# node.net
KiCad netlist of a schematic drawn in Altium Designer
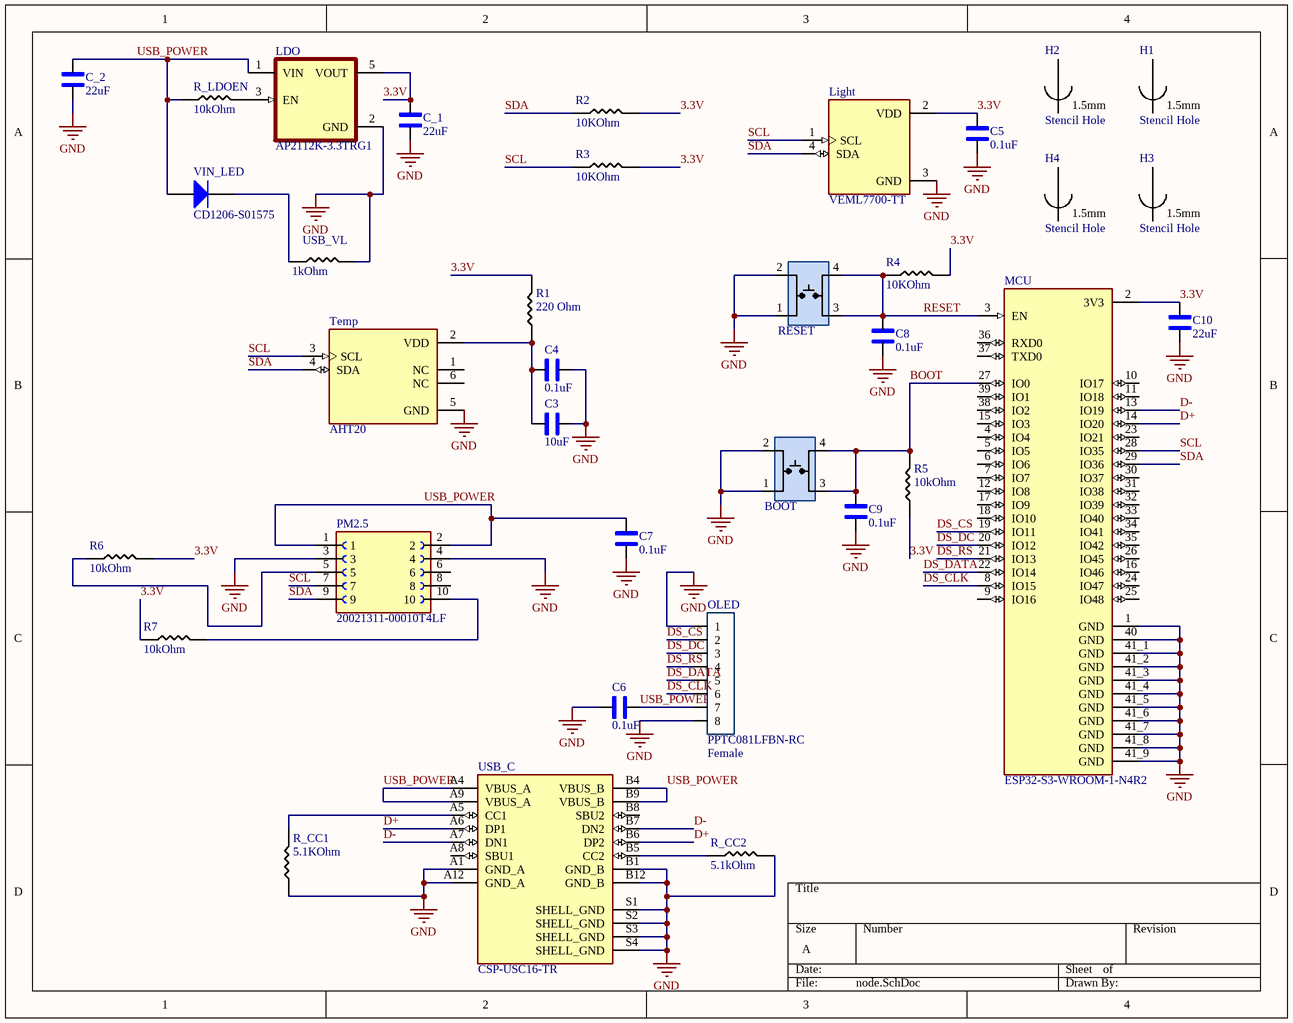
[diagram p0: node.SchDoc]

(export (version "E")
  (design (tool "Eeschema 10.0.6"))
  (components
    (comp (ref "BOOT")
      (value "TL3305AF160QG")
      (footprint "Switch_JLC")
      (description "Tactile Switch SPST-NO Top Actuated Surface Mount")
      (fields (field (name "MFR PART #") "KH-4.5X4.5X4.3H-STM") (field (name "LCSC PART#") "C2837550"))
      (libsource (lib "ECEN5730Lib_2023_01_DS") (part "SW_Push_Button_JLC"))
    )
    (comp (ref "C3")
      (value "10uF")
      (footprint "1206_Passive_Capacitor")
      (description "10uF ±10% 50V X5R 1206 Multilayer Ceramic Capacitors MLCC - SMD/SMT RoHS")
      (fields (field (name "LCSC PART#") "C13585") (field (name "MFR PART #") "CL31A106KBHNNNE"))
      (libsource (lib "ECEN5730Lib_2023_01_DS") (part "C_10uF_1206"))
    )
    (comp (ref "C4")
      (value "0.1uF")
      (footprint "1206_Passive_Capacitor")
      (description "10uF ±10% 50V X5R 1206 Multilayer Ceramic Capacitors MLCC - SMD/SMT RoHS")
      (fields (field (name "LCSC PART#") "C13585") (field (name "MFR PART #") "CL31A106KBHNNNE"))
      (libsource (lib "ECEN5730Lib_2023_01_DS") (part "C_10uF_1206"))
    )
    (comp (ref "C5")
      (value "0.1uF")
      (footprint "1206_Passive_Capacitor")
      (description "10uF ±10% 50V X5R 1206 Multilayer Ceramic Capacitors MLCC - SMD/SMT RoHS")
      (fields (field (name "LCSC PART#") "C13585") (field (name "MFR PART #") "CL31A106KBHNNNE"))
      (libsource (lib "ECEN5730Lib_2023_01_DS") (part "C_10uF_1206"))
    )
    (comp (ref "C6")
      (value "0.1uF")
      (footprint "1206_Passive_Capacitor")
      (description "10uF ±10% 50V X5R 1206 Multilayer Ceramic Capacitors MLCC - SMD/SMT RoHS")
      (fields (field (name "LCSC PART#") "C13585") (field (name "MFR PART #") "CL31A106KBHNNNE"))
      (libsource (lib "ECEN5730Lib_2023_01_DS") (part "C_10uF_1206"))
    )
    (comp (ref "C7")
      (value "0.1uF")
      (footprint "1206_Passive_Capacitor")
      (description "10uF ±10% 50V X5R 1206 Multilayer Ceramic Capacitors MLCC - SMD/SMT RoHS")
      (fields (field (name "LCSC PART#") "C13585") (field (name "MFR PART #") "CL31A106KBHNNNE"))
      (libsource (lib "ECEN5730Lib_2023_01_DS") (part "C_10uF_1206"))
    )
    (comp (ref "C8")
      (value "0.1uF")
      (footprint "1206_Passive_Capacitor")
      (description "10uF ±10% 50V X5R 1206 Multilayer Ceramic Capacitors MLCC - SMD/SMT RoHS")
      (fields (field (name "LCSC PART#") "C13585") (field (name "MFR PART #") "CL31A106KBHNNNE"))
      (libsource (lib "ECEN5730Lib_2023_01_DS") (part "C_10uF_1206"))
    )
    (comp (ref "C9")
      (value "0.1uF")
      (footprint "1206_Passive_Capacitor")
      (description "10uF ±10% 50V X5R 1206 Multilayer Ceramic Capacitors MLCC - SMD/SMT RoHS")
      (fields (field (name "LCSC PART#") "C13585") (field (name "MFR PART #") "CL31A106KBHNNNE"))
      (libsource (lib "ECEN5730Lib_2023_01_DS") (part "C_10uF_1206"))
    )
    (comp (ref "C10")
      (value "22uF")
      (footprint "1206_Passive_Capacitor")
      (description "10uF ±10% 50V X5R 1206 Multilayer Ceramic Capacitors MLCC - SMD/SMT RoHS")
      (fields (field (name "LCSC PART#") "C13585") (field (name "MFR PART #") "CL31A106KBHNNNE"))
      (libsource (lib "ECEN5730Lib_2023_01_DS") (part "C_10uF_1206"))
    )
    (comp (ref "C_1")
      (value "22uF")
      (footprint "1206_Passive_Capacitor")
      (description "22uF ±10% 25V X5R 1206 Multilayer Ceramic Capacitors MLCC - SMD/SMT RoHS")
      (fields (field (name "MFR PART #") "CL31A226KAHNNNE") (field (name "LCSC PART#") "C12891"))
      (libsource (lib "ECEN5730Lib_2023_01_DS") (part "C_22uF_1206"))
    )
    (comp (ref "C_2")
      (value "22uF")
      (footprint "1206_Passive_Capacitor")
      (description "22uF ±10% 25V X5R 1206 Multilayer Ceramic Capacitors MLCC - SMD/SMT RoHS")
      (fields (field (name "MFR PART #") "CL31A226KAHNNNE") (field (name "LCSC PART#") "C12891"))
      (libsource (lib "ECEN5730Lib_2023_01_DS") (part "C_22uF_1206"))
    )
    (comp (ref "H1")
      (value "Stencil Hole")
      (footprint "AlignmentHole_1.5mm")
      (description "Stencil Allignment hole for use with 1.5mm pin")
      (libsource (lib "ECEN5730Lib_2023_01_DS") (part "H_StencilAllignment_1.5mm"))
    )
    (comp (ref "H2")
      (value "Stencil Hole")
      (footprint "AlignmentHole_1.5mm")
      (description "Stencil Allignment hole for use with 1.5mm pin")
      (libsource (lib "ECEN5730Lib_2023_01_DS") (part "H_StencilAllignment_1.5mm"))
    )
    (comp (ref "H3")
      (value "Stencil Hole")
      (footprint "AlignmentHole_1.5mm")
      (description "Stencil Allignment hole for use with 1.5mm pin")
      (libsource (lib "ECEN5730Lib_2023_01_DS") (part "H_StencilAllignment_1.5mm"))
    )
    (comp (ref "H4")
      (value "Stencil Hole")
      (footprint "AlignmentHole_1.5mm")
      (description "Stencil Allignment hole for use with 1.5mm pin")
      (libsource (lib "ECEN5730Lib_2023_01_DS") (part "H_StencilAllignment_1.5mm"))
    )
    (comp (ref "LDO")
      (value "AP2112K-3.3TRG1")
      (footprint "AP2112K-3.3TRG1:SOT95P285X140-5N")
      (description "AP2112 Series 0.6 A 3.3 V Fixed Output SMT LDO Linear Regulator - SOT23-5")
      (fields (field (name "MF") "{'manufacturer': u'Diodes Inc.'}"))
      (libsource (lib "AP2112K-3.3TRG1") (part "AP2112K-3.3TRG1"))
    )
    (comp (ref "Light")
      (value "VEML7700-TT")
      (footprint "VEML7700-TT:XDCR_VEML7700-TT")
      (fields (field (name "MF") "{'manufacturer': u'Vishay Semiconductor'}"))
      (libsource (lib "*") (part "VEML7700-TT"))
    )
    (comp (ref "MCU")
      (value "ESP32-S3-WROOM-1-N4R2")
      (footprint "ESP32-S3-WROOM-1-N4R2:XCVR_ESP32-S3-WROOM-1-N4R2")
      (fields (field (name "MF") "{'manufacturer': u'Espressif Systems'}"))
      (libsource (lib "*") (part "ESP32-S3-WROOM-1-N4R2"))
    )
    (comp (ref "OLED")
      (value "PPTC081LFBN-RC")
      (footprint "8_PIN_100MIL - Female")
      (description "8 Position Header Connector 0.100\" (2.54mm) Through Hole Tin")
      (fields (field (name "LCSC PART#") "C27438") (field (name "ALTIUM_VALUE") "Female"))
      (libsource (lib "ECEN5730Lib_2023_01_DS") (part "JF_8_PIN_FEMALE"))
    )
    (comp (ref "PM2.5")
      (value "20021311-00010T4LF")
      (footprint "20021311-00010T4LF:AMPHENOL_20021311-00010T4LF")
      (fields (field (name "MF") "{'manufacturer': u'Amphenol ICC'}"))
      (libsource (lib "*") (part "20021311-00010T4LF"))
    )
    (comp (ref "R1")
      (value "220 Ohm")
      (footprint "1206_Passive_Resitor")
      (description "CHIP RESISTOR - SURFACE MOUNT 0OHMS ±1% 1/4W 1206 ROHS")
      (fields (field (name "MFR PART #") "1206W4F0000T5E") (field (name "LCSC PART#") "C17888"))
      (libsource (lib "ECEN5730Lib_2023_01_DS") (part "R_0Ohm_1206"))
    )
    (comp (ref "R2")
      (value "10KOhm")
      (footprint "1206_Passive_Resitor")
      (description "10 kOhms ±5% 0.25W, 1/4W Chip Resistor 1206 (3216 Metric) Automotive AEC-Q200 Thick Film")
      (fields (field (name "MFR PART #") "RMCF1206FT10K0") (field (name "LCSC PART#") "C17902"))
      (libsource (lib "ECEN5730Lib_2023_01_DS") (part "R_10KOhm_1206"))
    )
    (comp (ref "R3")
      (value "10KOhm")
      (footprint "1206_Passive_Resitor")
      (description "10 kOhms ±5% 0.25W, 1/4W Chip Resistor 1206 (3216 Metric) Automotive AEC-Q200 Thick Film")
      (fields (field (name "MFR PART #") "RMCF1206FT10K0") (field (name "LCSC PART#") "C17902"))
      (libsource (lib "ECEN5730Lib_2023_01_DS") (part "R_10KOhm_1206"))
    )
    (comp (ref "R4")
      (value "10KOhm")
      (footprint "1206_Passive_Resitor")
      (description "10 kOhms ±5% 0.25W, 1/4W Chip Resistor 1206 (3216 Metric) Automotive AEC-Q200 Thick Film")
      (fields (field (name "MFR PART #") "RMCF1206FT10K0") (field (name "LCSC PART#") "C17902"))
      (libsource (lib "ECEN5730Lib_2023_01_DS") (part "R_10KOhm_1206"))
    )
    (comp (ref "R5")
      (value "10kOhm")
      (footprint "1206_Passive_Resitor")
      (description "CHIP RESISTOR - SURFACE MOUNT 0OHMS ±1% 1/4W 1206 ROHS")
      (fields (field (name "MFR PART #") "1206W4F0000T5E") (field (name "LCSC PART#") "C17888"))
      (libsource (lib "ECEN5730Lib_2023_01_DS") (part "R_0Ohm_1206"))
    )
    (comp (ref "R6")
      (value "10kOhm")
      (footprint "1206_Passive_Resitor")
      (description "CHIP RESISTOR - SURFACE MOUNT 0OHMS ±1% 1/4W 1206 ROHS")
      (fields (field (name "MFR PART #") "1206W4F0000T5E") (field (name "LCSC PART#") "C17888"))
      (libsource (lib "ECEN5730Lib_2023_01_DS") (part "R_0Ohm_1206"))
    )
    (comp (ref "R7")
      (value "10kOhm")
      (footprint "1206_Passive_Resitor")
      (description "CHIP RESISTOR - SURFACE MOUNT 0OHMS ±1% 1/4W 1206 ROHS")
      (fields (field (name "MFR PART #") "1206W4F0000T5E") (field (name "LCSC PART#") "C17888"))
      (libsource (lib "ECEN5730Lib_2023_01_DS") (part "R_0Ohm_1206"))
    )
    (comp (ref "RESET")
      (value "TL3305AF160QG")
      (footprint "Switch_JLC")
      (description "Tactile Switch SPST-NO Top Actuated Surface Mount")
      (fields (field (name "MFR PART #") "KH-4.5X4.5X4.3H-STM") (field (name "LCSC PART#") "C2837550"))
      (libsource (lib "ECEN5730Lib_2023_01_DS") (part "SW_Push_Button_JLC"))
    )
    (comp (ref "R_CC1")
      (value "5.1KOhm")
      (footprint "1206_Passive_Resitor")
      (description "100kΩ ±1% 0.25W ±100ppm/℃ 1206 Chip Resistor - Surface Mount RoHS")
      (fields (field (name "LCSC PART#") "C17900") (field (name "MFR PART #") "1206W4F1003T5E"))
      (libsource (lib "ECEN5730Lib_2023_01_DS") (part "R_100KOhm_1206"))
    )
    (comp (ref "R_CC2")
      (value "5.1kOhm")
      (footprint "1206_Passive_Resitor")
      (description "100kΩ ±1% 0.25W ±100ppm/℃ 1206 Chip Resistor - Surface Mount RoHS")
      (fields (field (name "LCSC PART#") "C17900") (field (name "MFR PART #") "1206W4F1003T5E"))
      (libsource (lib "ECEN5730Lib_2023_01_DS") (part "R_100KOhm_1206"))
    )
    (comp (ref "R_LDOEN")
      (value "10kOhm")
      (footprint "1206_Passive_Resitor")
      (description "1Ω ±5% 0.25W ±400ppm/℃ 1206 Chip Resistor - Surface Mount RoHS")
      (fields (field (name "LCSC PART#") "C1409") (field (name "MFR PART #") "1206W4J010JT5E"))
      (libsource (lib "ECEN5730Lib_2023_01_DS") (part "R_1Ohm_1206"))
    )
    (comp (ref "Temp")
      (value "AHT20")
      (footprint "AHT20:PSON100P300X300X110-6N")
      (description "Temperature and Humidity sensor")
      (fields (field (name "MF") "{'manufacturer': u'Asair'}"))
      (libsource (lib "*") (part "AHT20"))
    )
    (comp (ref "USB_C")
      (value "CSP-USC16-TR")
      (footprint "CSP-USC16-TR:VALCON_CSP-USC16-TR")
      (fields (field (name "MF") "{'manufacturer': u'Valcon'}"))
      (libsource (lib "*") (part "CSP-USC16-TR"))
    )
    (comp (ref "USB_VL")
      (value "1kOhm")
      (footprint "1206_Passive_Resitor")
      (description "100Ω ±1% 0.25W ±100ppm/℃ 1206 Chip Resistor - Surface Mount RoHS")
      (fields (field (name "LCSC PART#") "C17901") (field (name "MFR PART #") "1206W4F1000T5E"))
      (libsource (lib "ECEN5730Lib_2023_01_DS") (part "R_100Ohm_1206"))
    )
    (comp (ref "VIN_LED")
      (value "CD1206-S01575")
      (footprint "BOUR-CD1206-S01575-2_L")
      (description "75 V Small Signal Switching Diode, 150 mA, 2.5 uA, 1026 Molded Package, RoHS, Tape and Reel")
      (fields (field (name "MANUFACTURER") "Bourns"))
      (libsource (lib "Altium Content Vault") (part "BOUR-A1K2-2"))
    )
  )
  (nets
    (net (code "1") (name "/3.3V") (class "Default")
      (node (ref "C10") (pin "2") (pinfunction "2_2") (pintype "passive"))
      (node (ref "C5") (pin "2") (pinfunction "2_2") (pintype "passive"))
      (node (ref "C_1") (pin "2") (pinfunction "2_2") (pintype "passive"))
      (node (ref "LDO") (pin "5") (pinfunction "VOUT_5") (pintype "power_in"))
      (node (ref "Light") (pin "2") (pinfunction "VDD_2") (pintype "power_in"))
      (node (ref "MCU") (pin "2") (pinfunction "3V3_2") (pintype "power_in"))
      (node (ref "R1") (pin "2") (pinfunction "2_2") (pintype "passive"))
      (node (ref "R2") (pin "2") (pinfunction "2_2") (pintype "passive"))
      (node (ref "R3") (pin "2") (pinfunction "2_2") (pintype "passive"))
      (node (ref "R4") (pin "2") (pinfunction "2_2") (pintype "passive"))
      (node (ref "R5") (pin "1") (pinfunction "1_1") (pintype "passive"))
      (node (ref "R6") (pin "2") (pinfunction "2_2") (pintype "passive"))
      (node (ref "R7") (pin "1") (pinfunction "1_1") (pintype "passive"))
    )
    (net (code "3") (name "/BOOT") (class "Default")
      (node (ref "BOOT") (pin "3") (pinfunction "3_3") (pintype "passive"))
      (node (ref "BOOT") (pin "4") (pinfunction "4_4") (pintype "passive"))
      (node (ref "C9") (pin "2") (pinfunction "2_2") (pintype "passive"))
      (node (ref "MCU") (pin "27") (pinfunction "IO0_27") (pintype "bidirectional"))
      (node (ref "R5") (pin "2") (pinfunction "2_2") (pintype "passive"))
    )
    (net (code "4") (name "/D+") (class "Default")
      (node (ref "MCU") (pin "14") (pinfunction "IO20_14") (pintype "bidirectional"))
      (node (ref "USB_C") (pin "A6") (pinfunction "DP1_A6") (pintype "bidirectional"))
      (node (ref "USB_C") (pin "B6") (pinfunction "DP2_B6") (pintype "bidirectional"))
    )
    (net (code "5") (name "/D-") (class "Default")
      (node (ref "MCU") (pin "13") (pinfunction "IO19_13") (pintype "bidirectional"))
      (node (ref "USB_C") (pin "A7") (pinfunction "DN1_A7") (pintype "bidirectional"))
      (node (ref "USB_C") (pin "B7") (pinfunction "DN2_B7") (pintype "bidirectional"))
    )
    (net (code "6") (name "/DS_CLK") (class "Default")
      (node (ref "MCU") (pin "8") (pinfunction "IO15_8") (pintype "bidirectional"))
      (node (ref "OLED") (pin "6") (pinfunction "6_6") (pintype "passive"))
    )
    (net (code "7") (name "/DS_CS") (class "Default")
      (node (ref "MCU") (pin "19") (pinfunction "IO11_19") (pintype "bidirectional"))
      (node (ref "OLED") (pin "2") (pinfunction "2_2") (pintype "passive"))
    )
    (net (code "8") (name "/DS_DATA") (class "Default")
      (node (ref "MCU") (pin "22") (pinfunction "IO14_22") (pintype "bidirectional"))
      (node (ref "OLED") (pin "5") (pinfunction "5_5") (pintype "passive"))
    )
    (net (code "9") (name "/DS_DC") (class "Default")
      (node (ref "MCU") (pin "20") (pinfunction "IO12_20") (pintype "bidirectional"))
      (node (ref "OLED") (pin "3") (pinfunction "3_3") (pintype "passive"))
    )
    (net (code "10") (name "/DS_RS") (class "Default")
      (node (ref "MCU") (pin "21") (pinfunction "IO13_21") (pintype "bidirectional"))
      (node (ref "OLED") (pin "4") (pinfunction "4_4") (pintype "passive"))
    )
    (net (code "11") (name "/RESET") (class "Default")
      (node (ref "C8") (pin "2") (pinfunction "2_2") (pintype "passive"))
      (node (ref "MCU") (pin "3") (pinfunction "EN_3") (pintype "input"))
      (node (ref "R4") (pin "1") (pinfunction "1_1") (pintype "passive"))
      (node (ref "RESET") (pin "3") (pinfunction "3_3") (pintype "passive"))
      (node (ref "RESET") (pin "4") (pinfunction "4_4") (pintype "passive"))
    )
    (net (code "12") (name "/SCL") (class "Default")
      (node (ref "Light") (pin "1") (pinfunction "SCL_1") (pintype "input"))
      (node (ref "MCU") (pin "28") (pinfunction "IO35_28") (pintype "bidirectional"))
      (node (ref "PM2.5") (pin "7") (pinfunction "7_7") (pintype "passive"))
      (node (ref "R3") (pin "1") (pinfunction "1_1") (pintype "passive"))
      (node (ref "Temp") (pin "3") (pinfunction "SCL_3") (pintype "input"))
    )
    (net (code "13") (name "/SDA") (class "Default")
      (node (ref "Light") (pin "4") (pinfunction "SDA_4") (pintype "bidirectional"))
      (node (ref "MCU") (pin "29") (pinfunction "IO36_29") (pintype "bidirectional"))
      (node (ref "PM2.5") (pin "9") (pinfunction "9_9") (pintype "passive"))
      (node (ref "R2") (pin "1") (pinfunction "1_1") (pintype "passive"))
      (node (ref "Temp") (pin "4") (pinfunction "SDA_4") (pintype "bidirectional"))
    )
    (net (code "14") (name "/USB_POWER") (class "Default")
      (node (ref "C6") (pin "2") (pinfunction "2_2") (pintype "passive"))
      (node (ref "C7") (pin "2") (pinfunction "2_2") (pintype "passive"))
      (node (ref "C_2") (pin "2") (pinfunction "2_2") (pintype "passive"))
      (node (ref "LDO") (pin "1") (pinfunction "VIN_1") (pintype "power_in"))
      (node (ref "OLED") (pin "7") (pinfunction "7_7") (pintype "passive"))
      (node (ref "PM2.5") (pin "1") (pinfunction "1_1") (pintype "passive"))
      (node (ref "PM2.5") (pin "2") (pinfunction "2_2") (pintype "passive"))
      (node (ref "R_LDOEN") (pin "1") (pinfunction "1_1") (pintype "passive"))
      (node (ref "USB_C") (pin "A4") (pinfunction "VBUS_A_A4") (pintype "power_in"))
      (node (ref "USB_C") (pin "A9") (pinfunction "VBUS_A_A9") (pintype "power_in"))
      (node (ref "USB_C") (pin "B4") (pinfunction "VBUS_B_B4") (pintype "power_in"))
      (node (ref "USB_C") (pin "B9") (pinfunction "VBUS_B_B9") (pintype "power_in"))
      (node (ref "VIN_LED") (pin "1") (pinfunction "A_1") (pintype "passive"))
    )
    (net (code "15") (name "GND") (class "Default")
      (node (ref "BOOT") (pin "1") (pinfunction "1_1") (pintype "passive"))
      (node (ref "BOOT") (pin "2") (pinfunction "2_2") (pintype "passive"))
      (node (ref "C10") (pin "1") (pinfunction "1_1") (pintype "passive"))
      (node (ref "C3") (pin "2") (pinfunction "2_2") (pintype "passive"))
      (node (ref "C4") (pin "2") (pinfunction "2_2") (pintype "passive"))
      (node (ref "C5") (pin "1") (pinfunction "1_1") (pintype "passive"))
      (node (ref "C6") (pin "1") (pinfunction "1_1") (pintype "passive"))
      (node (ref "C7") (pin "1") (pinfunction "1_1") (pintype "passive"))
      (node (ref "C8") (pin "1") (pinfunction "1_1") (pintype "passive"))
      (node (ref "C9") (pin "1") (pinfunction "1_1") (pintype "passive"))
      (node (ref "C_1") (pin "1") (pinfunction "1_1") (pintype "passive"))
      (node (ref "C_2") (pin "1") (pinfunction "1_1") (pintype "passive"))
      (node (ref "LDO") (pin "2") (pinfunction "GND_2") (pintype "power_in"))
      (node (ref "Light") (pin "3") (pinfunction "GND_3") (pintype "power_in"))
      (node (ref "MCU") (pin "1") (pinfunction "GND_1") (pintype "power_in"))
      (node (ref "MCU") (pin "40") (pinfunction "GND_40") (pintype "power_in"))
      (node (ref "MCU") (pin "41_1") (pinfunction "GND_41_1") (pintype "power_in"))
      (node (ref "MCU") (pin "41_2") (pinfunction "GND_41_2") (pintype "power_in"))
      (node (ref "MCU") (pin "41_3") (pinfunction "GND_41_3") (pintype "power_in"))
      (node (ref "MCU") (pin "41_4") (pinfunction "GND_41_4") (pintype "power_in"))
      (node (ref "MCU") (pin "41_5") (pinfunction "GND_41_5") (pintype "power_in"))
      (node (ref "MCU") (pin "41_6") (pinfunction "GND_41_6") (pintype "power_in"))
      (node (ref "MCU") (pin "41_7") (pinfunction "GND_41_7") (pintype "power_in"))
      (node (ref "MCU") (pin "41_8") (pinfunction "GND_41_8") (pintype "power_in"))
      (node (ref "MCU") (pin "41_9") (pinfunction "GND_41_9") (pintype "power_in"))
      (node (ref "OLED") (pin "1") (pinfunction "1_1") (pintype "passive"))
      (node (ref "OLED") (pin "8") (pinfunction "8_8") (pintype "passive"))
      (node (ref "PM2.5") (pin "3") (pinfunction "3_3") (pintype "passive"))
      (node (ref "PM2.5") (pin "4") (pinfunction "4_4") (pintype "passive"))
      (node (ref "RESET") (pin "1") (pinfunction "1_1") (pintype "passive"))
      (node (ref "RESET") (pin "2") (pinfunction "2_2") (pintype "passive"))
      (node (ref "R_CC1") (pin "1") (pinfunction "1_1") (pintype "passive"))
      (node (ref "R_CC2") (pin "2") (pinfunction "2_2") (pintype "passive"))
      (node (ref "Temp") (pin "5") (pinfunction "GND_5") (pintype "power_in"))
      (node (ref "USB_C") (pin "A1") (pinfunction "GND_A_A1") (pintype "power_in"))
      (node (ref "USB_C") (pin "A12") (pinfunction "GND_A_A12") (pintype "power_in"))
      (node (ref "USB_C") (pin "B1") (pinfunction "GND_B_B1") (pintype "power_in"))
      (node (ref "USB_C") (pin "B12") (pinfunction "GND_B_B12") (pintype "power_in"))
      (node (ref "USB_C") (pin "S1") (pinfunction "SHELL_GND_S1") (pintype "power_in"))
      (node (ref "USB_C") (pin "S2") (pinfunction "SHELL_GND_S2") (pintype "power_in"))
      (node (ref "USB_C") (pin "S3") (pinfunction "SHELL_GND_S3") (pintype "power_in"))
      (node (ref "USB_C") (pin "S4") (pinfunction "SHELL_GND_S4") (pintype "power_in"))
      (node (ref "USB_VL") (pin "2") (pinfunction "2_2") (pintype "passive"))
    )
    (net (code "16") (name "Net-(LDO-EN)") (class "Default")
      (node (ref "LDO") (pin "3") (pinfunction "EN_3") (pintype "input"))
      (node (ref "R_LDOEN") (pin "2") (pinfunction "2_2") (pintype "passive"))
    )
    (net (code "17") (name "Net-(PM2.5-Pad5)") (class "Default")
      (node (ref "PM2.5") (pin "5") (pinfunction "5_5") (pintype "passive"))
      (node (ref "R6") (pin "1") (pinfunction "1_1") (pintype "passive"))
    )
    (net (code "18") (name "Net-(PM2.5-Pad10)") (class "Default")
      (node (ref "PM2.5") (pin "10") (pinfunction "10_10") (pintype "passive"))
      (node (ref "R7") (pin "2") (pinfunction "2_2") (pintype "passive"))
    )
    (net (code "19") (name "Net-(Temp-VDD)") (class "Default")
      (node (ref "C3") (pin "1") (pinfunction "1_1") (pintype "passive"))
      (node (ref "C4") (pin "1") (pinfunction "1_1") (pintype "passive"))
      (node (ref "R1") (pin "1") (pinfunction "1_1") (pintype "passive"))
      (node (ref "Temp") (pin "2") (pinfunction "VDD_2") (pintype "power_in"))
    )
    (net (code "20") (name "Net-(USB_C-CC1)") (class "Default")
      (node (ref "R_CC1") (pin "2") (pinfunction "2_2") (pintype "passive"))
      (node (ref "USB_C") (pin "A5") (pinfunction "CC1_A5") (pintype "bidirectional"))
    )
    (net (code "21") (name "Net-(USB_C-CC2)") (class "Default")
      (node (ref "R_CC2") (pin "1") (pinfunction "1_1") (pintype "passive"))
      (node (ref "USB_C") (pin "B5") (pinfunction "CC2_B5") (pintype "bidirectional"))
    )
    (net (code "22") (name "Net-(VIN_LED-K)") (class "Default")
      (node (ref "USB_VL") (pin "1") (pinfunction "1_1") (pintype "passive"))
      (node (ref "VIN_LED") (pin "2") (pinfunction "K_2") (pintype "passive"))
    )
    (net (code "23") (name "unconnected-(MCU-IO1-Pad39)") (class "Default")
      (node (ref "MCU") (pin "39") (pinfunction "IO1_39") (pintype "bidirectional"))
    )
    (net (code "24") (name "unconnected-(MCU-IO2-Pad38)") (class "Default")
      (node (ref "MCU") (pin "38") (pinfunction "IO2_38") (pintype "bidirectional"))
    )
    (net (code "25") (name "unconnected-(MCU-IO3-Pad15)") (class "Default")
      (node (ref "MCU") (pin "15") (pinfunction "IO3_15") (pintype "bidirectional"))
    )
    (net (code "26") (name "unconnected-(MCU-IO4-Pad4)") (class "Default")
      (node (ref "MCU") (pin "4") (pinfunction "IO4_4") (pintype "bidirectional"))
    )
    (net (code "27") (name "unconnected-(MCU-IO5-Pad5)") (class "Default")
      (node (ref "MCU") (pin "5") (pinfunction "IO5_5") (pintype "bidirectional"))
    )
    (net (code "28") (name "unconnected-(MCU-IO6-Pad6)") (class "Default")
      (node (ref "MCU") (pin "6") (pinfunction "IO6_6") (pintype "bidirectional"))
    )
    (net (code "29") (name "unconnected-(MCU-IO7-Pad7)") (class "Default")
      (node (ref "MCU") (pin "7") (pinfunction "IO7_7") (pintype "bidirectional"))
    )
    (net (code "30") (name "unconnected-(MCU-IO8-Pad12)") (class "Default")
      (node (ref "MCU") (pin "12") (pinfunction "IO8_12") (pintype "bidirectional"))
    )
    (net (code "31") (name "unconnected-(MCU-IO9-Pad17)") (class "Default")
      (node (ref "MCU") (pin "17") (pinfunction "IO9_17") (pintype "bidirectional"))
    )
    (net (code "32") (name "unconnected-(MCU-IO10-Pad18)") (class "Default")
      (node (ref "MCU") (pin "18") (pinfunction "IO10_18") (pintype "bidirectional"))
    )
    (net (code "33") (name "unconnected-(MCU-IO16-Pad9)") (class "Default")
      (node (ref "MCU") (pin "9") (pinfunction "IO16_9") (pintype "bidirectional"))
    )
    (net (code "34") (name "unconnected-(MCU-IO17-Pad10)") (class "Default")
      (node (ref "MCU") (pin "10") (pinfunction "IO17_10") (pintype "bidirectional"))
    )
    (net (code "35") (name "unconnected-(MCU-IO18-Pad11)") (class "Default")
      (node (ref "MCU") (pin "11") (pinfunction "IO18_11") (pintype "bidirectional"))
    )
    (net (code "36") (name "unconnected-(MCU-IO21-Pad23)") (class "Default")
      (node (ref "MCU") (pin "23") (pinfunction "IO21_23") (pintype "bidirectional"))
    )
    (net (code "37") (name "unconnected-(MCU-IO37-Pad30)") (class "Default")
      (node (ref "MCU") (pin "30") (pinfunction "IO37_30") (pintype "bidirectional"))
    )
    (net (code "38") (name "unconnected-(MCU-IO38-Pad31)") (class "Default")
      (node (ref "MCU") (pin "31") (pinfunction "IO38_31") (pintype "bidirectional"))
    )
    (net (code "39") (name "unconnected-(MCU-IO39-Pad32)") (class "Default")
      (node (ref "MCU") (pin "32") (pinfunction "IO39_32") (pintype "bidirectional"))
    )
    (net (code "40") (name "unconnected-(MCU-IO40-Pad33)") (class "Default")
      (node (ref "MCU") (pin "33") (pinfunction "IO40_33") (pintype "bidirectional"))
    )
    (net (code "41") (name "unconnected-(MCU-IO41-Pad34)") (class "Default")
      (node (ref "MCU") (pin "34") (pinfunction "IO41_34") (pintype "bidirectional"))
    )
    (net (code "42") (name "unconnected-(MCU-IO42-Pad35)") (class "Default")
      (node (ref "MCU") (pin "35") (pinfunction "IO42_35") (pintype "bidirectional"))
    )
    (net (code "43") (name "unconnected-(MCU-IO45-Pad26)") (class "Default")
      (node (ref "MCU") (pin "26") (pinfunction "IO45_26") (pintype "bidirectional"))
    )
    (net (code "44") (name "unconnected-(MCU-IO46-Pad16)") (class "Default")
      (node (ref "MCU") (pin "16") (pinfunction "IO46_16") (pintype "bidirectional"))
    )
    (net (code "45") (name "unconnected-(MCU-IO47-Pad24)") (class "Default")
      (node (ref "MCU") (pin "24") (pinfunction "IO47_24") (pintype "bidirectional"))
    )
    (net (code "46") (name "unconnected-(MCU-IO48-Pad25)") (class "Default")
      (node (ref "MCU") (pin "25") (pinfunction "IO48_25") (pintype "bidirectional"))
    )
    (net (code "47") (name "unconnected-(MCU-RXD0-Pad36)") (class "Default")
      (node (ref "MCU") (pin "36") (pinfunction "RXD0_36") (pintype "bidirectional"))
    )
    (net (code "48") (name "unconnected-(MCU-TXD0-Pad37)") (class "Default")
      (node (ref "MCU") (pin "37") (pinfunction "TXD0_37") (pintype "bidirectional"))
    )
    (net (code "49") (name "unconnected-(PM2.5-Pad6)") (class "Default")
      (node (ref "PM2.5") (pin "6") (pinfunction "6_6") (pintype "passive"))
    )
    (net (code "50") (name "unconnected-(PM2.5-Pad8)") (class "Default")
      (node (ref "PM2.5") (pin "8") (pinfunction "8_8") (pintype "passive"))
    )
    (net (code "51") (name "unconnected-(Temp-NC-Pad1)") (class "Default")
      (node (ref "Temp") (pin "1") (pinfunction "NC_1") (pintype "passive"))
    )
    (net (code "52") (name "unconnected-(Temp-NC-Pad6)") (class "Default")
      (node (ref "Temp") (pin "6") (pinfunction "NC_6") (pintype "passive"))
    )
    (net (code "53") (name "unconnected-(USB_C-SBU1-PadA8)") (class "Default")
      (node (ref "USB_C") (pin "A8") (pinfunction "SBU1_A8") (pintype "bidirectional"))
    )
    (net (code "54") (name "unconnected-(USB_C-SBU2-PadB8)") (class "Default")
      (node (ref "USB_C") (pin "B8") (pinfunction "SBU2_B8") (pintype "bidirectional"))
    )
  )
)
